# ATtiny841_StepperTesting_Packaged.net
KiCad netlist of a schematic drawn in EAGLE
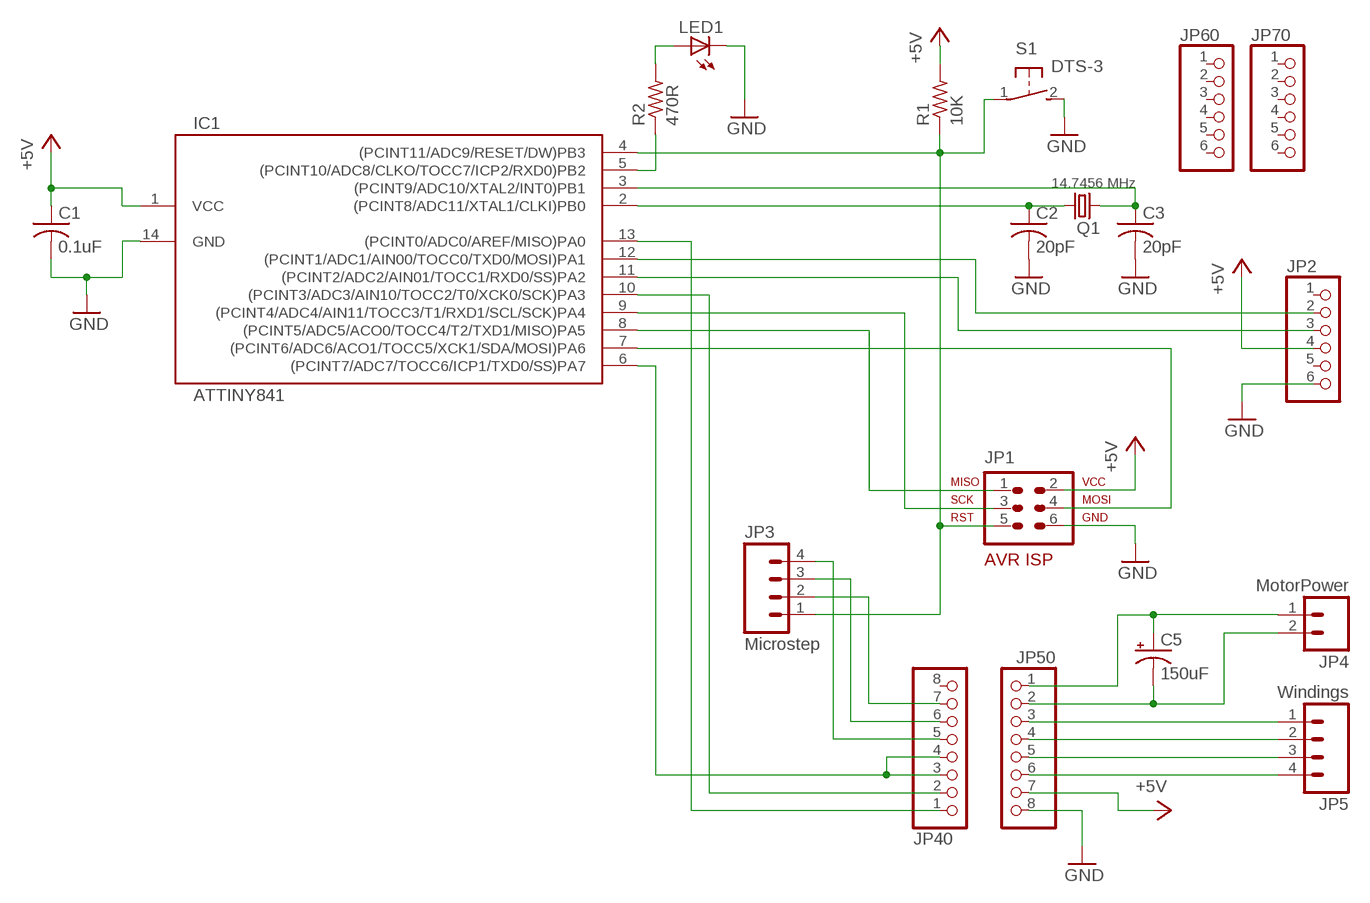
[diagram p0: schematic, sheet 1]

(export (version "E")
  (design (tool "Eeschema 10.0.6"))
  (components
    (comp (ref "C1")
      (value "0.1uF")
      (footprint "eagle-import:C025-024X044")
      (libsource (lib "eagle-import") (part "C025"))
    )
    (comp (ref "C2")
      (value "20pF")
      (footprint "eagle-import:C025-024X044")
      (libsource (lib "eagle-import") (part "C025"))
    )
    (comp (ref "C3")
      (value "20pF")
      (footprint "eagle-import:C025-024X044")
      (libsource (lib "eagle-import") (part "C025"))
    )
    (comp (ref "C5")
      (value "150uF")
      (footprint "eagle-import:E7,5-18")
      (libsource (lib "eagle-import") (part "CPOL-USE7.5-18"))
    )
    (comp (ref "IC1")
      (value "ATTINY841")
      (footprint "eagle-import:SOIC14")
      (libsource (lib "eagle-import") (part "ATTINY441/841-SSU"))
    )
    (comp (ref "JP1")
      (value "AVR-ISP-6VERT")
      (footprint "eagle-import:AVR-ISP-6")
      (libsource (lib "eagle-import") (part "AVR-ISP-6VERT"))
    )
    (comp (ref "JP2")
      (value "PINHD-1X6CB")
      (footprint "eagle-import:1X06-CLEANBIG")
      (libsource (lib "eagle-import") (part "PINHD-1X6CB"))
    )
    (comp (ref "JP3")
      (value "Microstep")
      (footprint "eagle-import:MOLEX-1X4")
      (libsource (lib "eagle-import") (part "M04POLAR"))
    )
    (comp (ref "JP4")
      (value "MotorPower")
      (footprint "eagle-import:MOLEX-1X2")
      (libsource (lib "eagle-import") (part "M02POLAR"))
    )
    (comp (ref "JP5")
      (value "Windings")
      (footprint "eagle-import:MOLEX-1X4")
      (libsource (lib "eagle-import") (part "M04POLAR"))
    )
    (comp (ref "JP40")
      (value "PINHD-1X8CLEANBIG")
      (footprint "eagle-import:1X08-CLEANBIG")
      (libsource (lib "eagle-import") (part "PINHD-1X8CLEANBIG"))
    )
    (comp (ref "JP50")
      (value "PINHD-1X8CLEANBIG")
      (footprint "eagle-import:1X08-CLEANBIG")
      (libsource (lib "eagle-import") (part "PINHD-1X8CLEANBIG"))
    )
    (comp (ref "JP60")
      (value "PINHD-1X6CB")
      (footprint "eagle-import:1X06-CLEANBIG")
      (libsource (lib "eagle-import") (part "PINHD-1X6CB"))
    )
    (comp (ref "JP70")
      (value "PINHD-1X6CB")
      (footprint "eagle-import:1X06-CLEANBIG")
      (libsource (lib "eagle-import") (part "PINHD-1X6CB"))
    )
    (comp (ref "LED1")
      (value "LED5MM")
      (footprint "eagle-import:LED5MM")
      (libsource (lib "eagle-import") (part "LED5MM"))
    )
    (comp (ref "Q1")
      (value "14.7456 MHz")
      (footprint "eagle-import:HC49_S")
      (libsource (lib "eagle-import") (part "CRYSTALHC49S"))
    )
    (comp (ref "R1")
      (value "10K")
      (footprint "eagle-import:0207_7")
      (libsource (lib "eagle-import") (part "R-US_0207/7"))
    )
    (comp (ref "R2")
      (value "470R")
      (footprint "eagle-import:0207_7")
      (libsource (lib "eagle-import") (part "R-US_0207/7"))
    )
    (comp (ref "S1")
      (value "DTS-3")
      (footprint "eagle-import:DTS-3")
      (libsource (lib "eagle-import") (part "DTS-3"))
    )
  )
  (nets
    (net (code "1") (name "+5V") (class "Default")
      (node (ref "C1") (pin "1") (pinfunction "1_1") (pintype "passive"))
      (node (ref "IC1") (pin "1") (pinfunction "VCC_1") (pintype "bidirectional"))
      (node (ref "JP1") (pin "2") (pinfunction "2_2") (pintype "passive"))
      (node (ref "JP2") (pin "4") (pinfunction "4_4") (pintype "passive"))
      (node (ref "JP50") (pin "7") (pinfunction "7_7") (pintype "passive"))
      (node (ref "R1") (pin "2") (pinfunction "2_2") (pintype "passive"))
    )
    (net (code "2") (name "GND") (class "Default")
      (node (ref "C1") (pin "2") (pinfunction "2_2") (pintype "passive"))
      (node (ref "C2") (pin "2") (pinfunction "2_2") (pintype "passive"))
      (node (ref "C3") (pin "2") (pinfunction "2_2") (pintype "passive"))
      (node (ref "IC1") (pin "14") (pinfunction "GND_14") (pintype "bidirectional"))
      (node (ref "JP1") (pin "6") (pinfunction "6_6") (pintype "passive"))
      (node (ref "JP2") (pin "6") (pinfunction "6_6") (pintype "passive"))
      (node (ref "JP50") (pin "8") (pinfunction "8_8") (pintype "passive"))
      (node (ref "LED1") (pin "K") (pinfunction "C_K") (pintype "passive"))
      (node (ref "S1") (pin "2") (pinfunction "2_2") (pintype "passive"))
    )
    (net (code "3") (name "Net-(C5-Pad+)") (class "Default")
      (node (ref "C5") (pin "+") (pinfunction "+_+") (pintype "passive"))
      (node (ref "JP4") (pin "1") (pinfunction "1_1") (pintype "passive"))
      (node (ref "JP50") (pin "1") (pinfunction "1_1") (pintype "passive"))
    )
    (net (code "4") (name "Net-(C5-Pad-)") (class "Default")
      (node (ref "C5") (pin "-") (pinfunction "-_-") (pintype "passive"))
      (node (ref "JP4") (pin "2") (pinfunction "2_2") (pintype "passive"))
      (node (ref "JP50") (pin "2") (pinfunction "2_2") (pintype "passive"))
    )
    (net (code "5") (name "Net-(IC1-(PCINT0{slash}ADC0{slash}AREF{slash}MISO)PA0)") (class "Default")
      (node (ref "IC1") (pin "13") (pinfunction "(PCINT0/ADC0/AREF/MISO)PA0_13") (pintype "bidirectional"))
      (node (ref "JP40") (pin "1") (pinfunction "1_1") (pintype "passive"))
    )
    (net (code "6") (name "Net-(IC1-(PCINT1{slash}ADC1{slash}AIN00{slash}TOCC0{slash}TXD0{slash}MOSI)PA1)") (class "Default")
      (node (ref "IC1") (pin "12") (pinfunction "(PCINT1/ADC1/AIN00/TOCC0/TXD0/MOSI)PA1_12") (pintype "bidirectional"))
      (node (ref "JP2") (pin "2") (pinfunction "2_2") (pintype "passive"))
    )
    (net (code "7") (name "Net-(IC1-(PCINT2{slash}ADC2{slash}AIN01{slash}TOCC1{slash}RXD0{slash}SS)PA2)") (class "Default")
      (node (ref "IC1") (pin "11") (pinfunction "(PCINT2/ADC2/AIN01/TOCC1/RXD0/SS)PA2_11") (pintype "bidirectional"))
      (node (ref "JP2") (pin "3") (pinfunction "3_3") (pintype "passive"))
    )
    (net (code "8") (name "Net-(IC1-(PCINT3{slash}ADC3{slash}AIN10{slash}TOCC2{slash}T0{slash}XCK0{slash}SCK)PA3)") (class "Default")
      (node (ref "IC1") (pin "10") (pinfunction "(PCINT3/ADC3/AIN10/TOCC2/T0/XCK0/SCK)PA3_10") (pintype "bidirectional"))
      (node (ref "JP40") (pin "2") (pinfunction "2_2") (pintype "passive"))
    )
    (net (code "9") (name "Net-(IC1-(PCINT4{slash}ADC4{slash}AIN11{slash}TOCC3{slash}T1{slash}RXD1{slash}SCL{slash}SCK)PA4)") (class "Default")
      (node (ref "IC1") (pin "9") (pinfunction "(PCINT4/ADC4/AIN11/TOCC3/T1/RXD1/SCL/SCK)PA4_9") (pintype "bidirectional"))
      (node (ref "JP1") (pin "3") (pinfunction "3_3") (pintype "passive"))
    )
    (net (code "10") (name "Net-(IC1-(PCINT5{slash}ADC5{slash}ACO0{slash}TOCC4{slash}T2{slash}TXD1{slash}MISO)PA5)") (class "Default")
      (node (ref "IC1") (pin "8") (pinfunction "(PCINT5/ADC5/ACO0/TOCC4/T2/TXD1/MISO)PA5_8") (pintype "bidirectional"))
      (node (ref "JP1") (pin "1") (pinfunction "1_1") (pintype "passive"))
    )
    (net (code "11") (name "Net-(IC1-(PCINT6{slash}ADC6{slash}ACO1{slash}TOCC5{slash}XCK1{slash}SDA{slash}MOSI)PA6)") (class "Default")
      (node (ref "IC1") (pin "7") (pinfunction "(PCINT6/ADC6/ACO1/TOCC5/XCK1/SDA/MOSI)PA6_7") (pintype "bidirectional"))
      (node (ref "JP1") (pin "4") (pinfunction "4_4") (pintype "passive"))
    )
    (net (code "12") (name "Net-(IC1-(PCINT7{slash}ADC7{slash}TOCC6{slash}ICP1{slash}TXD0{slash}SS)PA7)") (class "Default")
      (node (ref "IC1") (pin "6") (pinfunction "(PCINT7/ADC7/TOCC6/ICP1/TXD0/SS)PA7_6") (pintype "bidirectional"))
      (node (ref "JP40") (pin "3") (pinfunction "3_3") (pintype "passive"))
      (node (ref "JP40") (pin "4") (pinfunction "4_4") (pintype "passive"))
    )
    (net (code "13") (name "Net-(IC1-(PCINT8{slash}ADC11{slash}XTAL1{slash}CLKI)PB0)") (class "Default")
      (node (ref "C2") (pin "1") (pinfunction "1_1") (pintype "passive"))
      (node (ref "IC1") (pin "2") (pinfunction "(PCINT8/ADC11/XTAL1/CLKI)PB0_2") (pintype "bidirectional"))
      (node (ref "Q1") (pin "2") (pinfunction "2_2") (pintype "passive"))
    )
    (net (code "14") (name "Net-(IC1-(PCINT9{slash}ADC10{slash}XTAL2{slash}INT0)PB1)") (class "Default")
      (node (ref "C3") (pin "1") (pinfunction "1_1") (pintype "passive"))
      (node (ref "IC1") (pin "3") (pinfunction "(PCINT9/ADC10/XTAL2/INT0)PB1_3") (pintype "bidirectional"))
      (node (ref "Q1") (pin "1") (pinfunction "1_1") (pintype "passive"))
    )
    (net (code "15") (name "Net-(IC1-(PCINT10{slash}ADC8{slash}CLKO{slash}TOCC7{slash}ICP2{slash}RXD0)PB2)") (class "Default")
      (node (ref "IC1") (pin "5") (pinfunction "(PCINT10/ADC8/CLKO/TOCC7/ICP2/RXD0)PB2_5") (pintype "bidirectional"))
      (node (ref "R2") (pin "1") (pinfunction "1_1") (pintype "passive"))
    )
    (net (code "16") (name "Net-(IC1-(PCINT11{slash}ADC9{slash}RESET{slash}DW)PB3)") (class "Default")
      (node (ref "IC1") (pin "4") (pinfunction "(PCINT11/ADC9/RESET/DW)PB3_4") (pintype "bidirectional"))
      (node (ref "JP1") (pin "5") (pinfunction "5_5") (pintype "passive"))
      (node (ref "JP3") (pin "1") (pinfunction "1_1") (pintype "passive"))
      (node (ref "R1") (pin "1") (pinfunction "1_1") (pintype "passive"))
      (node (ref "S1") (pin "1") (pinfunction "1_1") (pintype "passive"))
    )
    (net (code "17") (name "Net-(JP3-Pad2)") (class "Default")
      (node (ref "JP3") (pin "2") (pinfunction "2_2") (pintype "passive"))
      (node (ref "JP40") (pin "7") (pinfunction "7_7") (pintype "passive"))
    )
    (net (code "18") (name "Net-(JP3-Pad3)") (class "Default")
      (node (ref "JP3") (pin "3") (pinfunction "3_3") (pintype "passive"))
      (node (ref "JP40") (pin "6") (pinfunction "6_6") (pintype "passive"))
    )
    (net (code "19") (name "Net-(JP3-Pad4)") (class "Default")
      (node (ref "JP3") (pin "4") (pinfunction "4_4") (pintype "passive"))
      (node (ref "JP40") (pin "5") (pinfunction "5_5") (pintype "passive"))
    )
    (net (code "20") (name "Net-(JP5-Pad1)") (class "Default")
      (node (ref "JP5") (pin "1") (pinfunction "1_1") (pintype "passive"))
      (node (ref "JP50") (pin "3") (pinfunction "3_3") (pintype "passive"))
    )
    (net (code "21") (name "Net-(JP5-Pad2)") (class "Default")
      (node (ref "JP5") (pin "2") (pinfunction "2_2") (pintype "passive"))
      (node (ref "JP50") (pin "4") (pinfunction "4_4") (pintype "passive"))
    )
    (net (code "22") (name "Net-(JP5-Pad3)") (class "Default")
      (node (ref "JP5") (pin "3") (pinfunction "3_3") (pintype "passive"))
      (node (ref "JP50") (pin "5") (pinfunction "5_5") (pintype "passive"))
    )
    (net (code "23") (name "Net-(JP5-Pad4)") (class "Default")
      (node (ref "JP5") (pin "4") (pinfunction "4_4") (pintype "passive"))
      (node (ref "JP50") (pin "6") (pinfunction "6_6") (pintype "passive"))
    )
    (net (code "24") (name "Net-(LED1-PadA)") (class "Default")
      (node (ref "LED1") (pin "A") (pinfunction "A_A") (pintype "passive"))
      (node (ref "R2") (pin "2") (pinfunction "2_2") (pintype "passive"))
    )
    (net (code "25") (name "unconnected-(JP2-Pad1)") (class "Default")
      (node (ref "JP2") (pin "1") (pinfunction "1_1") (pintype "passive"))
    )
    (net (code "26") (name "unconnected-(JP2-Pad5)") (class "Default")
      (node (ref "JP2") (pin "5") (pinfunction "5_5") (pintype "passive"))
    )
    (net (code "27") (name "unconnected-(JP40-Pad8)") (class "Default")
      (node (ref "JP40") (pin "8") (pinfunction "8_8") (pintype "passive"))
    )
    (net (code "28") (name "unconnected-(JP60-Pad1)") (class "Default")
      (node (ref "JP60") (pin "1") (pinfunction "1_1") (pintype "passive"))
    )
    (net (code "29") (name "unconnected-(JP60-Pad2)") (class "Default")
      (node (ref "JP60") (pin "2") (pinfunction "2_2") (pintype "passive"))
    )
    (net (code "30") (name "unconnected-(JP60-Pad3)") (class "Default")
      (node (ref "JP60") (pin "3") (pinfunction "3_3") (pintype "passive"))
    )
    (net (code "31") (name "unconnected-(JP60-Pad4)") (class "Default")
      (node (ref "JP60") (pin "4") (pinfunction "4_4") (pintype "passive"))
    )
    (net (code "32") (name "unconnected-(JP60-Pad5)") (class "Default")
      (node (ref "JP60") (pin "5") (pinfunction "5_5") (pintype "passive"))
    )
    (net (code "33") (name "unconnected-(JP60-Pad6)") (class "Default")
      (node (ref "JP60") (pin "6") (pinfunction "6_6") (pintype "passive"))
    )
    (net (code "34") (name "unconnected-(JP70-Pad1)") (class "Default")
      (node (ref "JP70") (pin "1") (pinfunction "1_1") (pintype "passive"))
    )
    (net (code "35") (name "unconnected-(JP70-Pad2)") (class "Default")
      (node (ref "JP70") (pin "2") (pinfunction "2_2") (pintype "passive"))
    )
    (net (code "36") (name "unconnected-(JP70-Pad3)") (class "Default")
      (node (ref "JP70") (pin "3") (pinfunction "3_3") (pintype "passive"))
    )
    (net (code "37") (name "unconnected-(JP70-Pad4)") (class "Default")
      (node (ref "JP70") (pin "4") (pinfunction "4_4") (pintype "passive"))
    )
    (net (code "38") (name "unconnected-(JP70-Pad5)") (class "Default")
      (node (ref "JP70") (pin "5") (pinfunction "5_5") (pintype "passive"))
    )
    (net (code "39") (name "unconnected-(JP70-Pad6)") (class "Default")
      (node (ref "JP70") (pin "6") (pinfunction "6_6") (pintype "passive"))
    )
  )
)
